# 3_Audio_Codec.net
KiCad netlist of a schematic drawn in Altium Designer
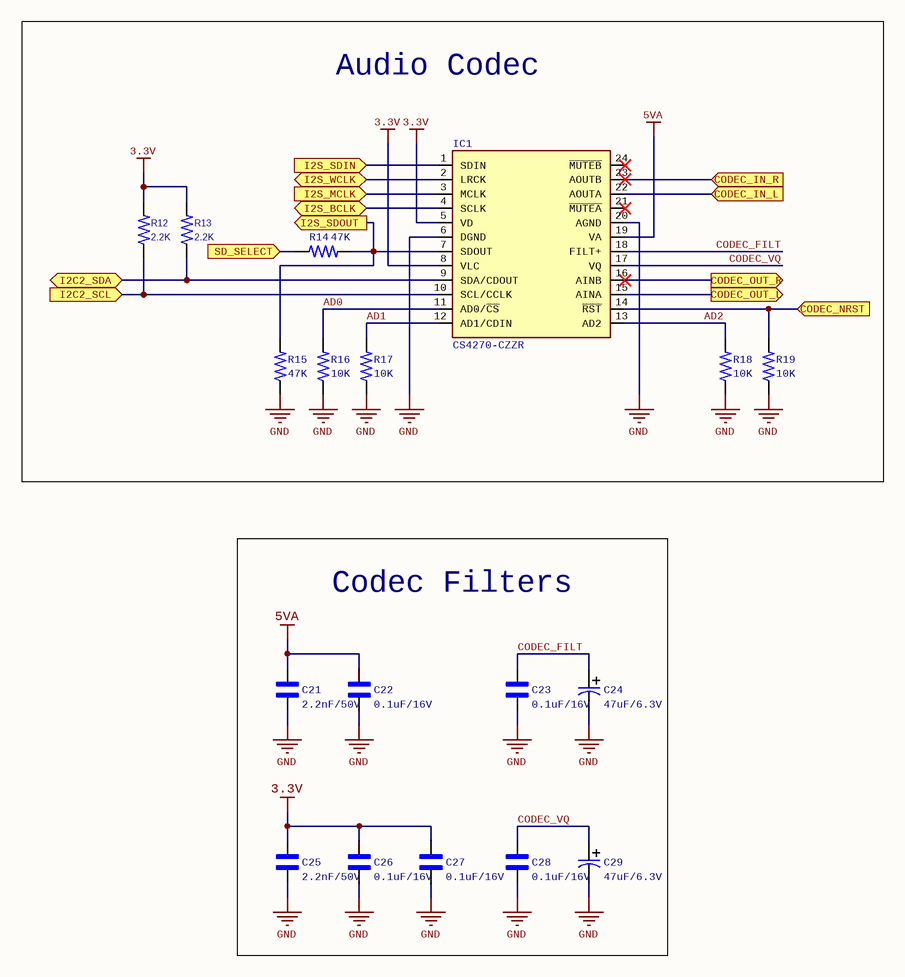
[diagram p0: [3] Audio Codec.SchDoc]

(export (version "E")
  (design (tool "Eeschema 10.0.6"))
  (components
    (comp (ref "C21")
      (value "2.2nF/50V")
      (footprint "C0603")
      (description "MLCC 2.2nF 10V X5R 10% 0603")
      (fields
        (field (name "MANUFACTURER") "Samsung")
        (field (name "MANUFACTURER PART NUMBER") "CL10B222KB8NFNC")
      )
      (libsource (lib "Capacitors") (part "C0603 2.2nF/50V"))
    )
    (comp (ref "C22")
      (value "0.1uF/16V")
      (footprint "C0603")
      (description "MLCC 0.1UF, 16V, X5R, 10%, 0603.")
      (fields
        (field (name "MANUFACTURER") "Kyocera AVX")
        (field (name "MANUFACTURER PART NUMBER") "0603YD104KAT2A")
      )
      (libsource (lib "Capacitors") (part "C0603 0.1uF/16V"))
    )
    (comp (ref "C23")
      (value "0.1uF/16V")
      (footprint "C0603")
      (description "MLCC 0.1UF, 16V, X5R, 10%, 0603.")
      (fields
        (field (name "MANUFACTURER") "Kyocera AVX")
        (field (name "MANUFACTURER PART NUMBER") "0603YD104KAT2A")
      )
      (libsource (lib "Capacitors") (part "C0603 0.1uF/16V"))
    )
    (comp (ref "C24")
      (value "47uF/6.3V")
      (footprint "EIA1206")
      (description "Tantalum Capacitors - Solid SMD 6.3V 47uF 10%")
      (fields
        (field (name "MANUFACTURER") "Kyocera AVX")
        (field (name "MANUFACTURER PART NUMBER") "TAJA476K006SNJV")
      )
      (libsource (lib "Capacitors") (part "TANT 47UF/6.3V"))
    )
    (comp (ref "C25")
      (value "2.2nF/50V")
      (footprint "C0603")
      (description "MLCC 2.2nF 10V X5R 10% 0603")
      (fields
        (field (name "MANUFACTURER") "Samsung")
        (field (name "MANUFACTURER PART NUMBER") "CL10B222KB8NFNC")
      )
      (libsource (lib "Capacitors") (part "C0603 2.2nF/50V"))
    )
    (comp (ref "C26")
      (value "0.1uF/16V")
      (footprint "C0603")
      (description "MLCC 0.1UF, 16V, X5R, 10%, 0603.")
      (fields
        (field (name "MANUFACTURER") "Kyocera AVX")
        (field (name "MANUFACTURER PART NUMBER") "0603YD104KAT2A")
      )
      (libsource (lib "Capacitors") (part "C0603 0.1uF/16V"))
    )
    (comp (ref "C27")
      (value "0.1uF/16V")
      (footprint "C0603")
      (description "MLCC 0.1UF, 16V, X5R, 10%, 0603.")
      (fields
        (field (name "MANUFACTURER") "Kyocera AVX")
        (field (name "MANUFACTURER PART NUMBER") "0603YD104KAT2A")
      )
      (libsource (lib "Capacitors") (part "C0603 0.1uF/16V"))
    )
    (comp (ref "C28")
      (value "0.1uF/16V")
      (footprint "C0603")
      (description "MLCC 0.1UF, 16V, X5R, 10%, 0603.")
      (fields
        (field (name "MANUFACTURER") "Kyocera AVX")
        (field (name "MANUFACTURER PART NUMBER") "0603YD104KAT2A")
      )
      (libsource (lib "Capacitors") (part "C0603 0.1uF/16V"))
    )
    (comp (ref "C29")
      (value "47uF/6.3V")
      (footprint "EIA1206")
      (description "Tantalum Capacitors - Solid SMD 6.3V 47uF 10%")
      (fields
        (field (name "MANUFACTURER") "Kyocera AVX")
        (field (name "MANUFACTURER PART NUMBER") "TAJA476K006SNJV")
      )
      (libsource (lib "Capacitors") (part "TANT 47UF/6.3V"))
    )
    (comp (ref "IC1")
      (value "CS4270-CZZR")
      (footprint "TSSOP-24")
      (description "Audio Codec 2ADC / 2DAC 24-Bit 24-Pin TSSOP T/R (Alt: CS4270-CZZR)")
      (fields (field (name "MANUFACTURER") "Cirrus Logic"))
      (libsource (lib "IC Converter") (part "CS4270-CZZR"))
    )
    (comp (ref "R12")
      (value "2.2K")
      (footprint "R0603")
      (description "RES 0603 2.2K OHM 1% 1/10W")
      (fields
        (field (name "MANUFACTURER") "Yageo")
        (field (name "MANUFACTURER PART NUMBER") "RC0603FR-072K2L")
      )
      (libsource (lib "Resistors") (part "R0603 2.2K"))
    )
    (comp (ref "R13")
      (value "2.2K")
      (footprint "R0603")
      (description "RES 0603 2.2K OHM 1% 1/10W")
      (fields
        (field (name "MANUFACTURER") "Yageo")
        (field (name "MANUFACTURER PART NUMBER") "RC0603FR-072K2L")
      )
      (libsource (lib "Resistors") (part "R0603 2.2K"))
    )
    (comp (ref "R14")
      (value "47K")
      (footprint "R0603")
      (description "RES 0603 47K 1% 1/10W")
      (fields
        (field (name "MANUFACTURER") "Yageo")
        (field (name "MANUFACTURER PART NUMBER") "RC0603FR-0747KL")
      )
      (libsource (lib "Resistors") (part "R0603 47K"))
    )
    (comp (ref "R15")
      (value "47K")
      (footprint "R0603")
      (description "RES 0603 47K 1% 1/10W")
      (fields
        (field (name "MANUFACTURER") "Yageo")
        (field (name "MANUFACTURER PART NUMBER") "RC0603FR-0747KL")
      )
      (libsource (lib "Resistors") (part "R0603 47K"))
    )
    (comp (ref "R16")
      (value "10K")
      (footprint "R0603")
      (description "RES 0603 10K OHM 1% 1/10W")
      (fields
        (field (name "MANUFACTURER") "Yageo")
        (field (name "MANUFACTURER PART NUMBER") "RC0603FR-0710KP")
      )
      (libsource (lib "Resistors") (part "R0603 10K"))
    )
    (comp (ref "R17")
      (value "10K")
      (footprint "R0603")
      (description "RES 0603 10K OHM 1% 1/10W")
      (fields
        (field (name "MANUFACTURER") "Yageo")
        (field (name "MANUFACTURER PART NUMBER") "RC0603FR-0710KP")
      )
      (libsource (lib "Resistors") (part "R0603 10K"))
    )
    (comp (ref "R18")
      (value "10K")
      (footprint "R0603")
      (description "RES 0603 10K OHM 1% 1/10W")
      (fields
        (field (name "MANUFACTURER") "Yageo")
        (field (name "MANUFACTURER PART NUMBER") "RC0603FR-0710KP")
      )
      (libsource (lib "Resistors") (part "R0603 10K"))
    )
    (comp (ref "R19")
      (value "10K")
      (footprint "R0603")
      (description "RES 0603 10K OHM 1% 1/10W")
      (fields
        (field (name "MANUFACTURER") "Yageo")
        (field (name "MANUFACTURER PART NUMBER") "RC0603FR-0710KP")
      )
      (libsource (lib "Resistors") (part "R0603 10K"))
    )
  )
  (nets
    (net (code "1") (name "/AD0") (class "Default")
      (node (ref "IC1") (pin "11") (pinfunction "AD0/~{CS}_11") (pintype "passive"))
      (node (ref "R16") (pin "2") (pinfunction "2_2") (pintype "passive"))
    )
    (net (code "2") (name "/AD1") (class "Default")
      (node (ref "IC1") (pin "12") (pinfunction "AD1/CDIN_12") (pintype "passive"))
      (node (ref "R17") (pin "2") (pinfunction "2_2") (pintype "passive"))
    )
    (net (code "3") (name "/AD2") (class "Default")
      (node (ref "IC1") (pin "13") (pinfunction "AD2_13") (pintype "passive"))
      (node (ref "R18") (pin "2") (pinfunction "2_2") (pintype "passive"))
    )
    (net (code "4") (name "/CODEC_FILT") (class "Default")
      (node (ref "C23") (pin "2") (pinfunction "2_2") (pintype "passive"))
      (node (ref "C24") (pin "1") (pinfunction "1_1") (pintype "passive"))
      (node (ref "IC1") (pin "18") (pinfunction "FILT+_18") (pintype "passive"))
    )
    (net (code "5") (name "/CODEC_IN_L") (class "Default")
      (node (ref "IC1") (pin "22") (pinfunction "AOUTA_22") (pintype "passive"))
    )
    (net (code "6") (name "/CODEC_IN_R") (class "Default")
      (node (ref "IC1") (pin "23") (pinfunction "AOUTB_23") (pintype "passive+no_connect"))
    )
    (net (code "7") (name "/CODEC_NRST") (class "Default")
      (node (ref "IC1") (pin "14") (pinfunction "~{RST}_14") (pintype "passive"))
      (node (ref "R19") (pin "2") (pinfunction "2_2") (pintype "passive"))
    )
    (net (code "8") (name "/CODEC_OUT_L") (class "Default")
      (node (ref "IC1") (pin "15") (pinfunction "AINA_15") (pintype "passive"))
    )
    (net (code "9") (name "/CODEC_OUT_R") (class "Default")
      (node (ref "IC1") (pin "16") (pinfunction "AINB_16") (pintype "passive+no_connect"))
    )
    (net (code "10") (name "/CODEC_VQ") (class "Default")
      (node (ref "C28") (pin "2") (pinfunction "2_2") (pintype "passive"))
      (node (ref "C29") (pin "1") (pinfunction "1_1") (pintype "passive"))
      (node (ref "IC1") (pin "17") (pinfunction "VQ_17") (pintype "passive"))
    )
    (net (code "11") (name "/I2C2_SCL") (class "Default")
      (node (ref "IC1") (pin "10") (pinfunction "SCL/CCLK_10") (pintype "passive"))
      (node (ref "R12") (pin "1") (pinfunction "1_1") (pintype "passive"))
    )
    (net (code "12") (name "/I2C2_SDA") (class "Default")
      (node (ref "IC1") (pin "9") (pinfunction "SDA/CDOUT_9") (pintype "passive"))
      (node (ref "R13") (pin "1") (pinfunction "1_1") (pintype "passive"))
    )
    (net (code "13") (name "/I2S_BCLK") (class "Default")
      (node (ref "IC1") (pin "4") (pinfunction "SCLK_4") (pintype "passive"))
    )
    (net (code "14") (name "/I2S_MCLK") (class "Default")
      (node (ref "IC1") (pin "3") (pinfunction "MCLK_3") (pintype "passive"))
    )
    (net (code "15") (name "/I2S_SDIN") (class "Default")
      (node (ref "IC1") (pin "1") (pinfunction "SDIN_1") (pintype "passive"))
    )
    (net (code "16") (name "/I2S_SDOUT") (class "Default")
      (node (ref "IC1") (pin "7") (pinfunction "SDOUT_7") (pintype "passive"))
      (node (ref "R14") (pin "2") (pinfunction "2_2") (pintype "passive"))
      (node (ref "R15") (pin "2") (pinfunction "2_2") (pintype "passive"))
    )
    (net (code "17") (name "/I2S_WCLK") (class "Default")
      (node (ref "IC1") (pin "2") (pinfunction "LRCK_2") (pintype "passive"))
    )
    (net (code "18") (name "/SD_SELECT") (class "Default")
      (node (ref "R14") (pin "1") (pinfunction "1_1") (pintype "passive"))
    )
    (net (code "19") (name "3.3V") (class "Default")
      (node (ref "C25") (pin "1") (pinfunction "1_1") (pintype "passive"))
      (node (ref "C26") (pin "2") (pinfunction "2_2") (pintype "passive"))
      (node (ref "C27") (pin "2") (pinfunction "2_2") (pintype "passive"))
      (node (ref "IC1") (pin "5") (pinfunction "VD_5") (pintype "passive"))
      (node (ref "IC1") (pin "8") (pinfunction "VLC_8") (pintype "passive"))
      (node (ref "R12") (pin "2") (pinfunction "2_2") (pintype "passive"))
      (node (ref "R13") (pin "2") (pinfunction "2_2") (pintype "passive"))
    )
    (net (code "20") (name "5VA") (class "Default")
      (node (ref "C21") (pin "1") (pinfunction "1_1") (pintype "passive"))
      (node (ref "C22") (pin "2") (pinfunction "2_2") (pintype "passive"))
      (node (ref "IC1") (pin "19") (pinfunction "VA_19") (pintype "passive"))
    )
    (net (code "21") (name "GND") (class "Default")
      (node (ref "C21") (pin "2") (pinfunction "2_2") (pintype "passive"))
      (node (ref "C22") (pin "1") (pinfunction "1_1") (pintype "passive"))
      (node (ref "C23") (pin "1") (pinfunction "1_1") (pintype "passive"))
      (node (ref "C24") (pin "2") (pinfunction "2_2") (pintype "passive"))
      (node (ref "C25") (pin "2") (pinfunction "2_2") (pintype "passive"))
      (node (ref "C26") (pin "1") (pinfunction "1_1") (pintype "passive"))
      (node (ref "C27") (pin "1") (pinfunction "1_1") (pintype "passive"))
      (node (ref "C28") (pin "1") (pinfunction "1_1") (pintype "passive"))
      (node (ref "C29") (pin "2") (pinfunction "2_2") (pintype "passive"))
      (node (ref "IC1") (pin "20") (pinfunction "AGND_20") (pintype "passive"))
      (node (ref "IC1") (pin "6") (pinfunction "DGND_6") (pintype "passive"))
      (node (ref "R15") (pin "1") (pinfunction "1_1") (pintype "passive"))
      (node (ref "R16") (pin "1") (pinfunction "1_1") (pintype "passive"))
      (node (ref "R17") (pin "1") (pinfunction "1_1") (pintype "passive"))
      (node (ref "R18") (pin "1") (pinfunction "1_1") (pintype "passive"))
      (node (ref "R19") (pin "1") (pinfunction "1_1") (pintype "passive"))
    )
    (net (code "22") (name "unconnected-(IC1-~{MUTEA}-Pad21)") (class "Default")
      (node (ref "IC1") (pin "21") (pinfunction "~{MUTEA}_21") (pintype "passive+no_connect"))
    )
    (net (code "23") (name "unconnected-(IC1-~{MUTEB}-Pad24)") (class "Default")
      (node (ref "IC1") (pin "24") (pinfunction "~{MUTEB}_24") (pintype "passive+no_connect"))
    )
  )
)
